# 4g.net
KiCad netlist of a schematic drawn in Altium Designer
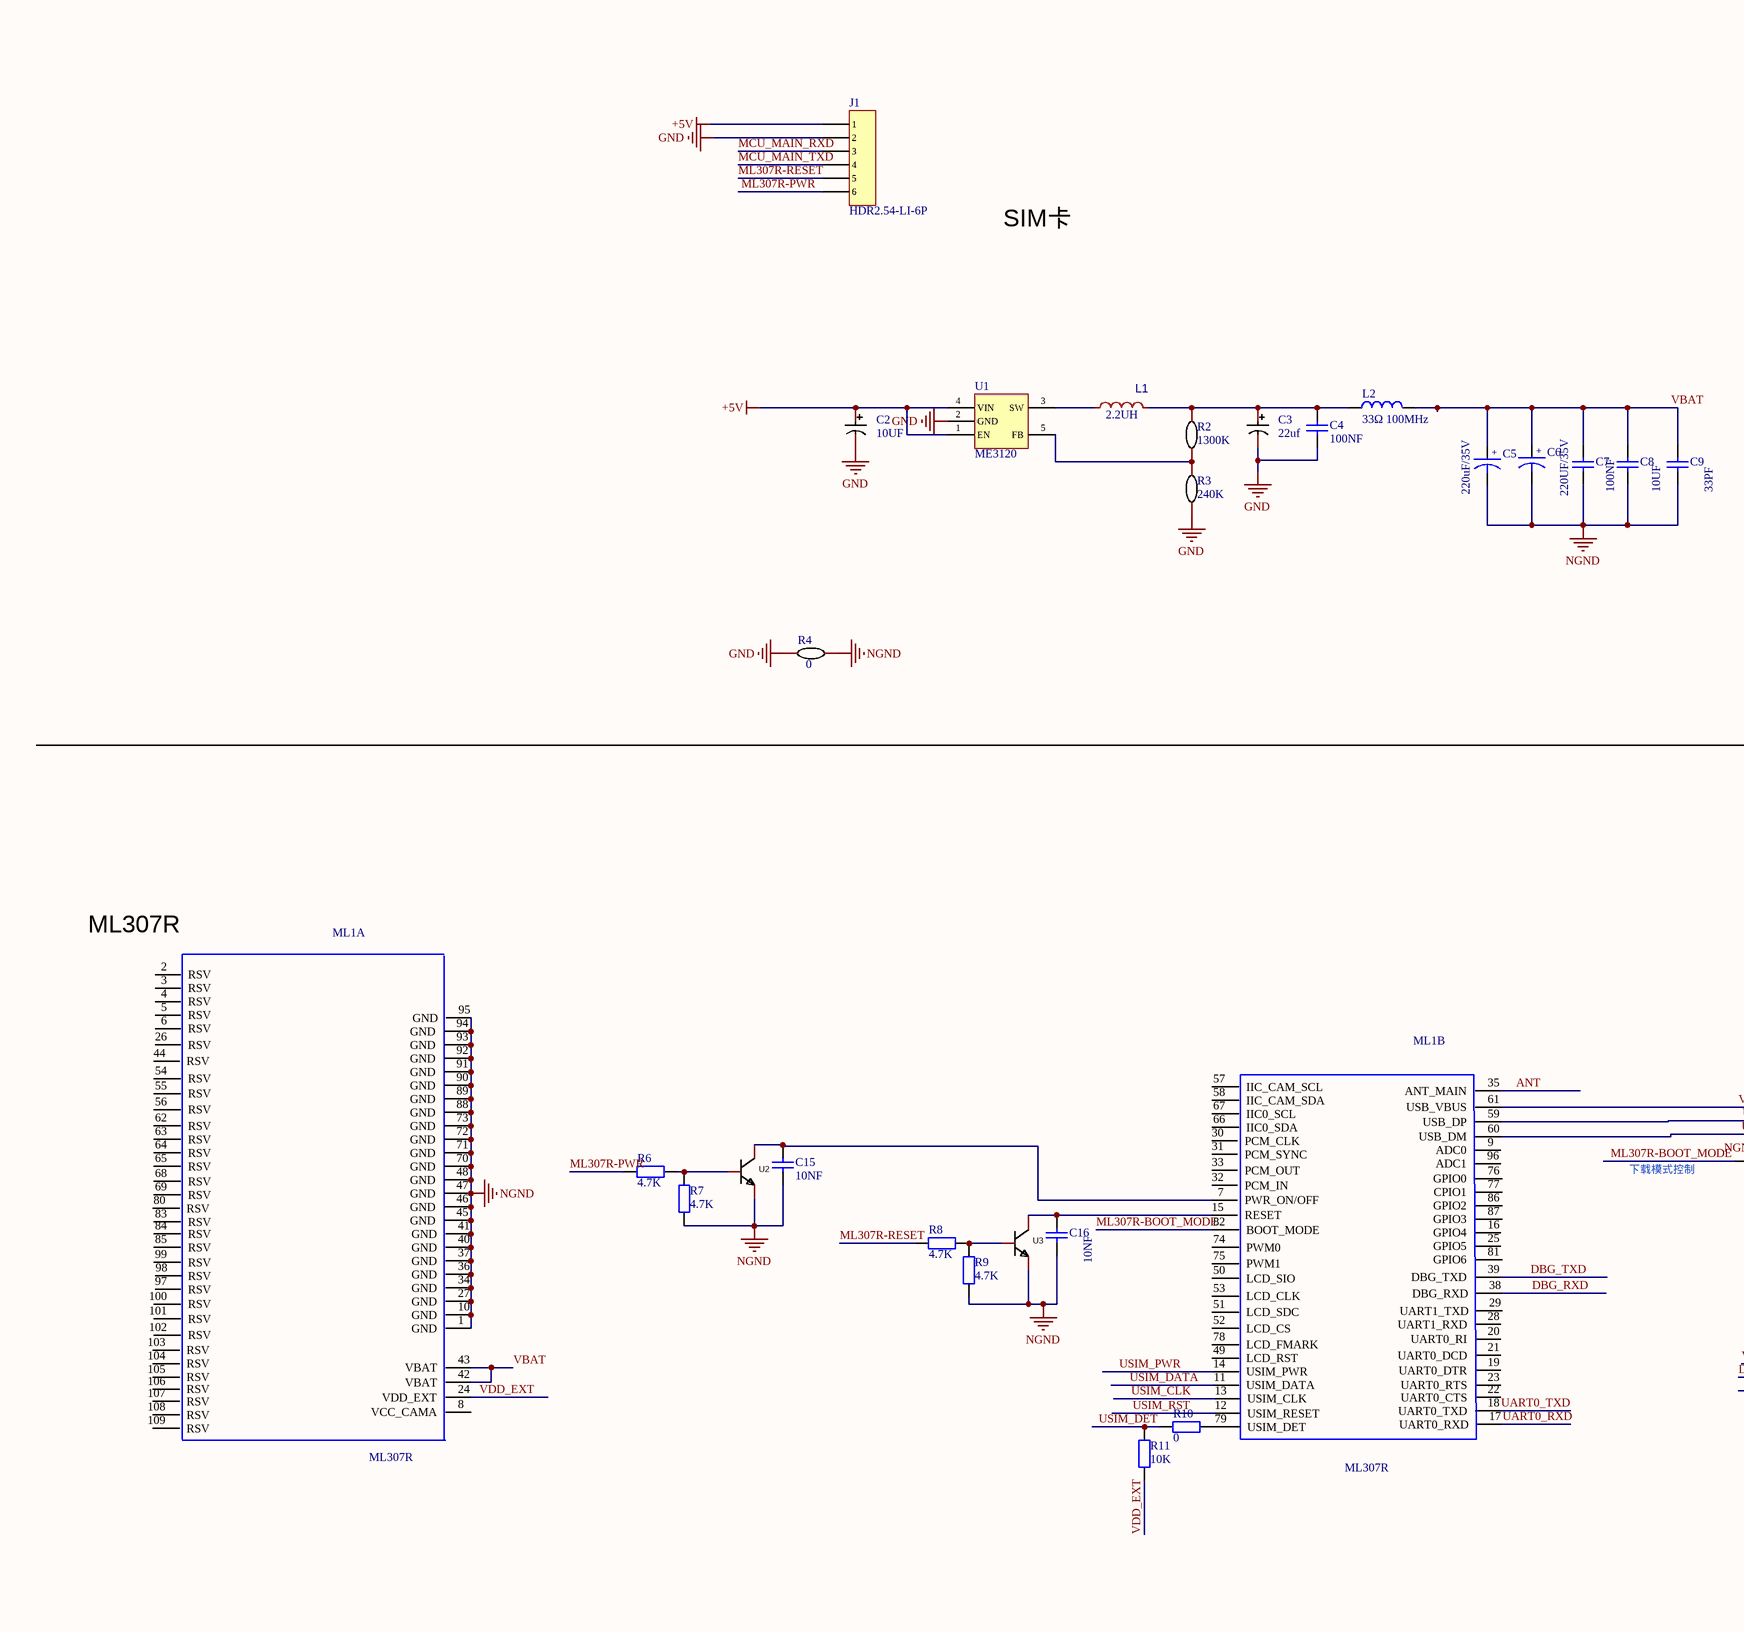
[diagram p0: 4g.SchDoc, left]
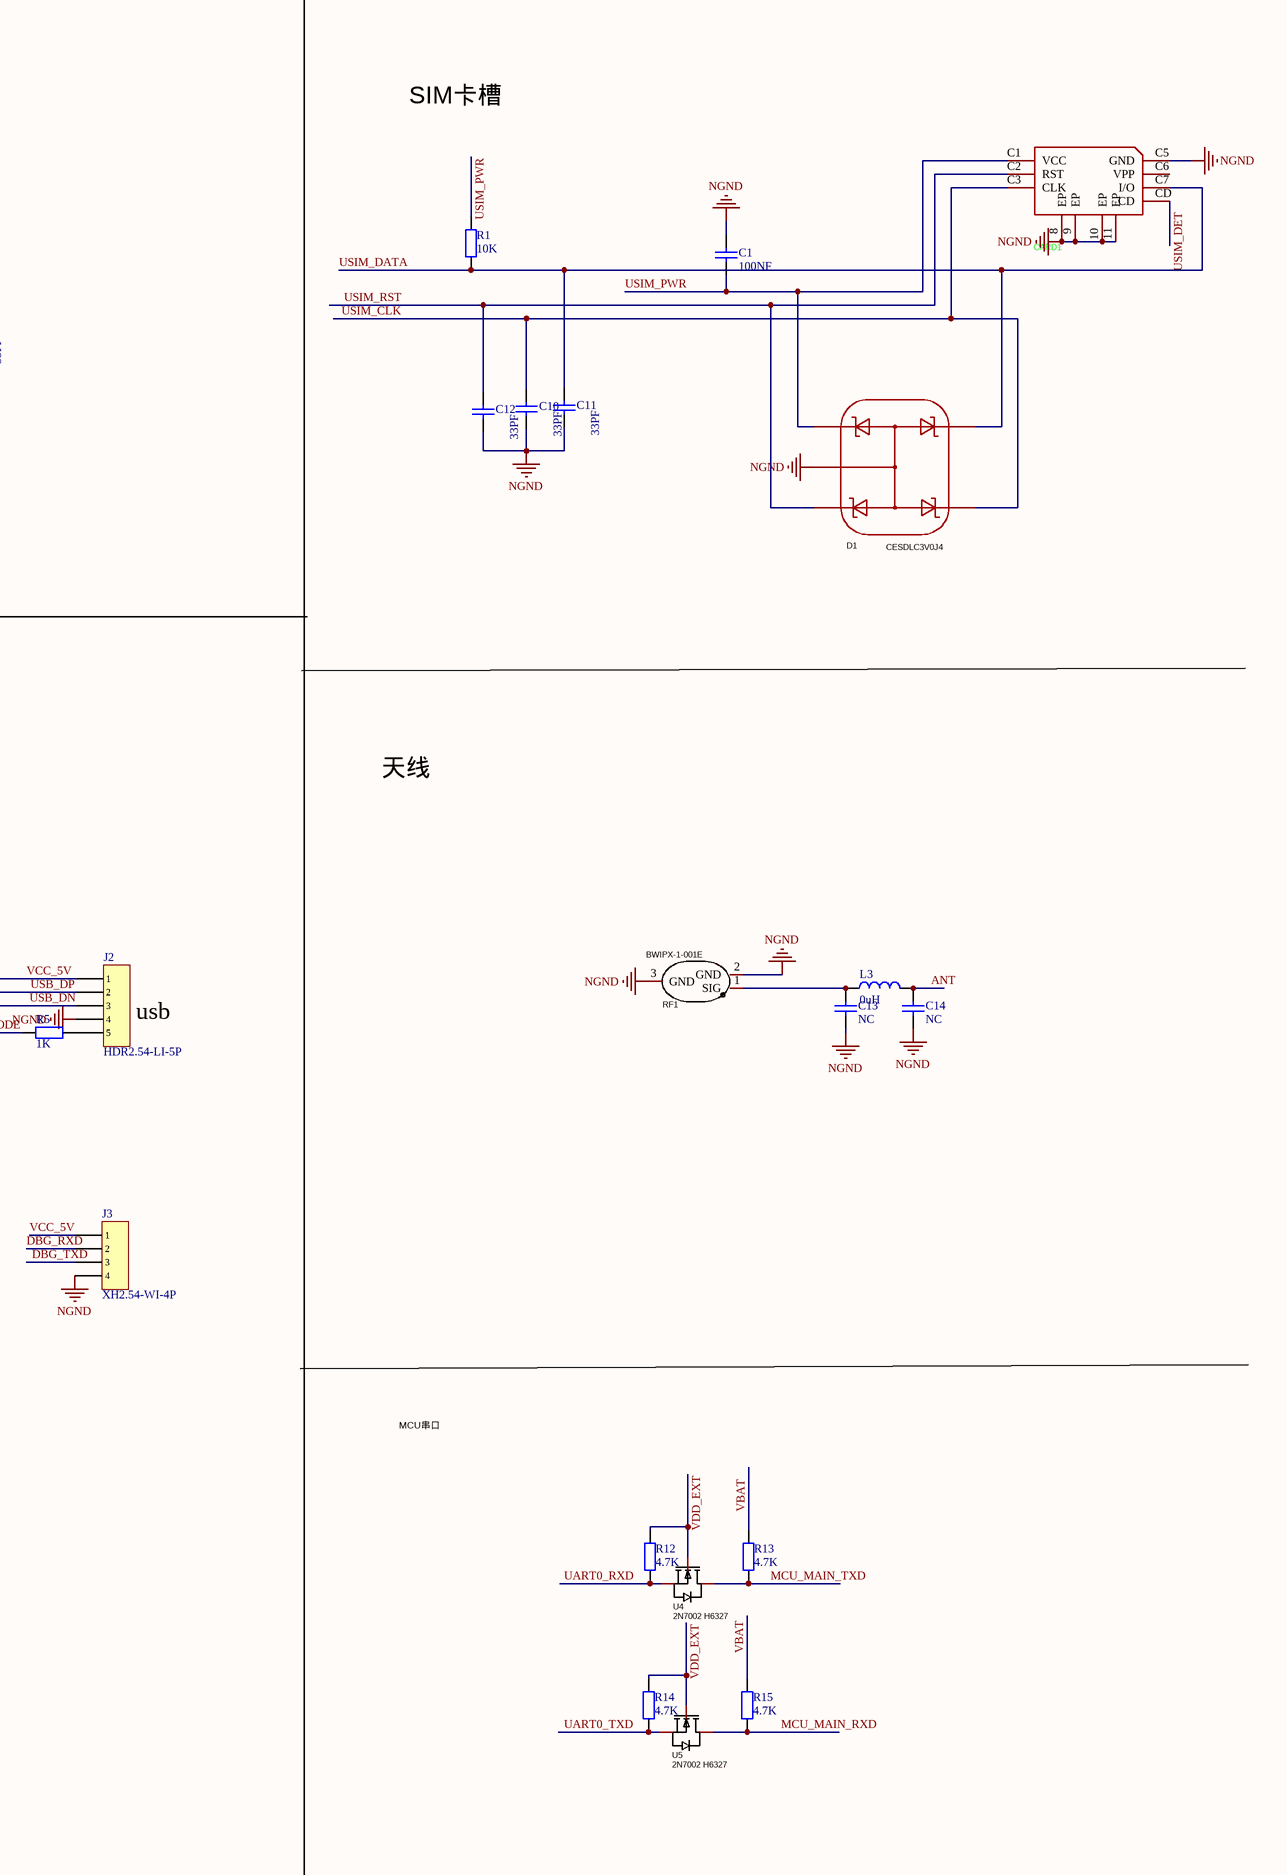
[diagram p1: 4g.SchDoc, right]

(export (version "E")
  (design (tool "Eeschema 10.0.6"))
  (components
    (comp (ref "C1")
      (value "100NF")
      (footprint "C-0603")
      (description "贴片电容")
      (libsource (lib "电容") (part "0603' 100pF 5% 50V NP0 车规"))
    )
    (comp (ref "C2")
      (value "10UF")
      (footprint "CA-3216")
      (fields
        (field (name "MANUFACTURER") "CapXon(丰宾)")
        (field (name "MANUFACTURER PART") "KF470M050E110A")
        (field (name "TOLERANCE") "±20%")
      )
      (libsource (lib "altium-import") (part "root_3_KF470M050E110A_"))
    )
    (comp (ref "C3")
      (value "22uf")
      (footprint "CA-3528")
      (fields
        (field (name "MANUFACTURER") "CapXon(丰宾)")
        (field (name "MANUFACTURER PART") "KF470M050E110A")
        (field (name "TOLERANCE") "±20%")
      )
      (libsource (lib "altium-import") (part "root_3_KF470M050E110A_"))
    )
    (comp (ref "C4")
      (value "100NF")
      (footprint "R-0603")
      (description "贴片电容")
      (libsource (lib "电容") (part "0603' 100pF 5% 50V NP0 车规"))
    )
    (comp (ref "C5")
      (value "220uF/35V")
      (footprint "CASE-B_3528")
      (description "电容")
      (libsource (lib "YLKG-51V1.0") (part "C电解电容_1"))
    )
    (comp (ref "C6")
      (value "220UF/35V")
      (footprint "CASE-B_3528")
      (description "电容")
      (libsource (lib "YLKG-51V1.0") (part "C电解电容_1"))
    )
    (comp (ref "C7")
      (value "100NF")
      (footprint "C-0603")
      (description "贴片电容")
      (libsource (lib "电容") (part "0603' 100pF 5% 50V NP0 车规"))
    )
    (comp (ref "C8")
      (value "10UF")
      (footprint "C-0603")
      (description "贴片电容")
      (libsource (lib "电容") (part "0603' 100pF 5% 50V NP0 车规"))
    )
    (comp (ref "C9")
      (value "33PF")
      (footprint "C-0603")
      (description "贴片电容")
      (libsource (lib "电容") (part "0603' 100pF 5% 50V NP0 车规"))
    )
    (comp (ref "C10")
      (value "33PF")
      (footprint "C-0603")
      (description "贴片电容")
      (libsource (lib "电容") (part "0603' 100pF 5% 50V NP0 车规"))
    )
    (comp (ref "C11")
      (value "33PF")
      (footprint "C-0603")
      (description "贴片电容")
      (libsource (lib "电容") (part "0603' 100pF 5% 50V NP0 车规"))
    )
    (comp (ref "C12")
      (value "33PF")
      (footprint "C-0603")
      (description "贴片电容")
      (libsource (lib "电容") (part "0603' 100pF 5% 50V NP0 车规"))
    )
    (comp (ref "C13")
      (value "NC")
      (footprint "C-0603")
      (description "贴片电容")
      (libsource (lib "电容") (part "0603' 100pF 5% 50V NP0 车规"))
    )
    (comp (ref "C14")
      (value "NC")
      (footprint "C-0603")
      (description "贴片电容")
      (libsource (lib "电容") (part "0603' 100pF 5% 50V NP0 车规"))
    )
    (comp (ref "C15")
      (value "10NF")
      (footprint "C-0603")
      (description "贴片电容")
      (libsource (lib "电容") (part "0603' 100pF 5% 50V NP0 车规"))
    )
    (comp (ref "C16")
      (value "10NF")
      (footprint "C-0603")
      (description "贴片电容")
      (libsource (lib "电容") (part "0603' 100pF 5% 50V NP0 车规"))
    )
    (comp (ref "CARD1")
      (value "SMN-303")
      (footprint "SIM-SMD_SMN-303")
      (fields (field (name "MANUFACTURER") "XUNPU(讯普)"))
      (libsource (lib "altium-import") (part "root_0_SMN-303_"))
    )
    (comp (ref "D1")
      (value "CESDLC3V0J4")
      (footprint "SOT-353_L2.1-W1.3-P0.65-LS2.3-BR")
      (fields (field (name "MANUFACTURER") "CJ(江苏长电/长晶)"))
      (libsource (lib "altium-import") (part "root_0_CESDLC3V0J4_"))
    )
    (comp (ref "J1")
      (value "HDR2.54-LI-6P")
      (footprint "HDR2.54-LI-6P")
      (description "直插立式单排针")
      (libsource (lib "排针排母") (part "HDR2.0-LI-6P"))
    )
    (comp (ref "J2")
      (value "HDR2.54-LI-5P")
      (footprint "2.54--5P")
      (description "直插立式单排针")
      (libsource (lib "排针排母") (part "HDR2.54-LI-5P"))
    )
    (comp (ref "J3")
      (value "XH2.54-WI-4P")
      (footprint "2.54--4P")
      (description "XH卧式直插座")
      (libsource (lib "通用连接器") (part "XH2.54-WI-4P"))
    )
    (comp (ref "L1")
      (value "2.2UH")
      (footprint "IND-SMD_L2.5-W2.0_MHCHL2520")
      (libsource (lib "altium-import") (part "root_0_FTC252012S2R2MBCA_"))
    )
    (comp (ref "L2")
      (value "33Ω 100MHz")
      (footprint "R-0805")
      (description "磁珠")
      (libsource (lib "电感") (part "0603' 33Ω 100MHz 3A 车规"))
    )
    (comp (ref "L3")
      (value "0uH")
      (footprint "R-0603")
      (description "通用电感")
      (libsource (lib "电感") (part "通用电感"))
    )
    (comp (ref "ML1")
      (value "ML307R")
      (footprint "MOD_ML307X_LGA109P")
      (description "MOD_ML307R_LCC48+LGA61_17.7mm*15.8mm")
      (fields (field (name "MANUFACTURER") "ML307X"))
      (libsource (lib "模块") (part "MOD_ML307X_LGA109P"))
    )
    (comp (ref "R1") (value "10K") (footprint "R-0603") (libsource (lib "电阻") (part "通用电阻")))
    (comp (ref "R2")
      (value "1300K")
      (footprint "R-0603")
      (description "电阻类型:厚膜电阻;阻值:0")
      (fields
        (field (name "MANUFACTURER") "UNI-ROYAL(厚声)")
        (field (name "MANUFACTURER PART") "0805W8F1002T5E")
      )
      (libsource (lib "altium-import") (part "root_3_0805W8F1002T5E_C17414_"))
    )
    (comp (ref "R3")
      (value "240K")
      (footprint "R-0603")
      (description "电阻类型:厚膜电阻;阻值:0")
      (fields
        (field (name "MANUFACTURER") "UNI-ROYAL(厚声)")
        (field (name "MANUFACTURER PART") "0805W8F1002T5E")
      )
      (libsource (lib "altium-import") (part "root_3_0805W8F1002T5E_C17414_"))
    )
    (comp (ref "R4")
      (value "0")
      (footprint "R-0805")
      (description "电阻类型:厚膜电阻;阻值:0")
      (fields
        (field (name "MANUFACTURER") "UNI-ROYAL(厚声)")
        (field (name "MANUFACTURER PART") "0805W8F1002T5E")
      )
      (libsource (lib "altium-import") (part "root_2_0805W8F1002T5E_C17414_"))
    )
    (comp (ref "R5")
      (value "1K")
      (footprint "R-0603")
      (description "贴片电阻，未编号，未录入华芯元件库，临时封装，包括0201，0402，0603，0805，1206，1210，1812，2010，2512")
      (libsource (lib "") (part "通用电阻_1"))
    )
    (comp (ref "R6")
      (value "4.7K")
      (footprint "R-0603")
      (description "贴片电阻，未编号，未录入华芯元件库，临时封装，包括0201，0402，0603，0805，1206，1210，1812，2010，2512")
      (libsource (lib "") (part "通用电阻_3"))
    )
    (comp (ref "R7")
      (value "4.7K")
      (footprint "R-0603")
      (description "贴片电阻，未编号，未录入华芯元件库，临时封装，包括0201，0402，0603，0805，1206，1210，1812，2010，2512")
      (libsource (lib "电阻") (part "通用电阻"))
    )
    (comp (ref "R8")
      (value "4.7K")
      (footprint "R-0603")
      (description "贴片电阻，未编号，未录入华芯元件库，临时封装，包括0201，0402，0603，0805，1206，1210，1812，2010，2512")
      (libsource (lib "") (part "通用电阻_3"))
    )
    (comp (ref "R9")
      (value "4.7K")
      (footprint "R-0603")
      (description "贴片电阻，未编号，未录入华芯元件库，临时封装，包括0201，0402，0603，0805，1206，1210，1812，2010，2512")
      (libsource (lib "电阻") (part "通用电阻"))
    )
    (comp (ref "R10")
      (value "0")
      (footprint "R-0603")
      (description "贴片电阻，未编号，未录入华芯元件库，临时封装，包括0201，0402，0603，0805，1206，1210，1812，2010，2512")
      (libsource (lib "") (part "通用电阻_1"))
    )
    (comp (ref "R11")
      (value "10K")
      (footprint "R-0603")
      (description "贴片电阻，未编号，未录入华芯元件库，临时封装，包括0201，0402，0603，0805，1206，1210，1812，2010，2512")
      (libsource (lib "") (part "通用电阻_2"))
    )
    (comp (ref "R12")
      (value "4.7K")
      (footprint "R-0603")
      (description "贴片电阻，未编号，未录入华芯元件库，临时封装，包括0201，0402，0603，0805，1206，1210，1812，2010，2512")
      (libsource (lib "电阻") (part "通用电阻"))
    )
    (comp (ref "R13")
      (value "4.7K")
      (footprint "R-0603")
      (description "贴片电阻，未编号，未录入华芯元件库，临时封装，包括0201，0402，0603，0805，1206，1210，1812，2010，2512")
      (libsource (lib "电阻") (part "通用电阻"))
    )
    (comp (ref "R14")
      (value "4.7K")
      (footprint "R-0603")
      (description "贴片电阻，未编号，未录入华芯元件库，临时封装，包括0201，0402，0603，0805，1206，1210，1812，2010，2512")
      (libsource (lib "电阻") (part "通用电阻"))
    )
    (comp (ref "R15")
      (value "4.7K")
      (footprint "R-0603")
      (description "贴片电阻，未编号，未录入华芯元件库，临时封装，包括0201，0402，0603，0805，1206，1210，1812，2010，2512")
      (libsource (lib "电阻") (part "通用电阻"))
    )
    (comp (ref "RF1")
      (value "BWIPX-1-001E")
      (footprint "IPEX-SMD_BWIPX-1-001E")
      (fields (field (name "MANUFACTURER") "BAT WIRELESS(蝙蝠无线)"))
      (libsource (lib "altium-import") (part "root_2_BWIPX-1-001E_"))
    )
    (comp (ref "U1")
      (value "ME3120")
      (footprint "SOT-23-5")
      (description "电源芯片")
      (libsource (lib "电源芯片") (part "ME3120"))
    )
    (comp (ref "U2")
      (value "SS8050")
      (footprint "SOT-23-3_(三极管)")
      (fields (field (name "MANUFACTURER") "宏迦橙"))
      (libsource (lib "晶体管") (part "SS8050 NPN SOT-23"))
    )
    (comp (ref "U3")
      (value "SS8050")
      (footprint "SOT-23-3_(三极管)")
      (fields (field (name "MANUFACTURER") "宏迦橙"))
      (libsource (lib "晶体管") (part "SS8050 NPN SOT-23"))
    )
    (comp (ref "U4")
      (value "2N7002 H6327")
      (footprint "PG-SOT23-3_L2.9-W1.3-P1.90-LS2.4-BR")
      (fields (field (name "MANUFACTURER") "Infineon(英飞凌)"))
      (libsource (lib "altium-import") (part "root_3_2N7002 H6327_"))
    )
    (comp (ref "U5")
      (value "2N7002 H6327")
      (footprint "PG-SOT23-3_L2.9-W1.3-P1.90-LS2.4-BR")
      (fields (field (name "MANUFACTURER") "Infineon(英飞凌)"))
      (libsource (lib "altium-import") (part "root_3_2N7002 H6327_"))
    )
  )
  (nets
    (net (code "1") (name "+5V") (class "Default")
      (node (ref "C2") (pin "1") (pinfunction "1_1") (pintype "passive"))
      (node (ref "J1") (pin "1") (pinfunction "1_1") (pintype "passive"))
      (node (ref "U1") (pin "1") (pinfunction "EN_1") (pintype "passive"))
      (node (ref "U1") (pin "4") (pinfunction "VIN_4") (pintype "passive"))
    )
    (net (code "2") (name "/ANT") (class "Default")
      (node (ref "C14") (pin "1") (pinfunction "1_1") (pintype "passive"))
      (node (ref "L3") (pin "2") (pinfunction "2_2") (pintype "passive"))
      (node (ref "ML1") (pin "35") (pinfunction "ANT_MAIN_35") (pintype "passive"))
    )
    (net (code "3") (name "/DBG_RXD") (class "Default")
      (node (ref "J3") (pin "2") (pinfunction "2_2") (pintype "passive"))
      (node (ref "ML1") (pin "38") (pinfunction "DBG_RXD_38") (pintype "passive"))
    )
    (net (code "4") (name "/DBG_TXD") (class "Default")
      (node (ref "J3") (pin "3") (pinfunction "3_3") (pintype "passive"))
      (node (ref "ML1") (pin "39") (pinfunction "DBG_TXD_39") (pintype "passive"))
    )
    (net (code "5") (name "/MCU_MAIN_RXD") (class "Default")
      (node (ref "J1") (pin "3") (pinfunction "3_3") (pintype "passive"))
      (node (ref "R15") (pin "1") (pinfunction "1_1") (pintype "passive"))
      (node (ref "U5") (pin "3") (pinfunction "D_3") (pintype "passive"))
    )
    (net (code "6") (name "/MCU_MAIN_TXD") (class "Default")
      (node (ref "J1") (pin "4") (pinfunction "4_4") (pintype "passive"))
      (node (ref "R13") (pin "1") (pinfunction "1_1") (pintype "passive"))
      (node (ref "U4") (pin "3") (pinfunction "D_3") (pintype "passive"))
    )
    (net (code "7") (name "/ML307R-BOOT_MODE") (class "Default")
      (node (ref "ML1") (pin "82") (pinfunction "BOOT_MODE_82") (pintype "passive"))
      (node (ref "R5") (pin "2") (pinfunction "2_2") (pintype "passive"))
    )
    (net (code "8") (name "/ML307R-PWR") (class "Default")
      (node (ref "J1") (pin "6") (pinfunction "6_6") (pintype "passive"))
      (node (ref "R6") (pin "1") (pinfunction "1_1") (pintype "passive"))
    )
    (net (code "9") (name "/ML307R-RESET") (class "Default")
      (node (ref "J1") (pin "5") (pinfunction "5_5") (pintype "passive"))
      (node (ref "R8") (pin "1") (pinfunction "1_1") (pintype "passive"))
    )
    (net (code "10") (name "/UART0_RXD") (class "Default")
      (node (ref "ML1") (pin "17") (pinfunction "UART0_RXD_17") (pintype "passive"))
      (node (ref "R12") (pin "1") (pinfunction "1_1") (pintype "passive"))
      (node (ref "U4") (pin "2") (pinfunction "S_2") (pintype "passive"))
    )
    (net (code "11") (name "/UART0_TXD") (class "Default")
      (node (ref "ML1") (pin "18") (pinfunction "UART0_TXD_18") (pintype "passive"))
      (node (ref "R14") (pin "1") (pinfunction "1_1") (pintype "passive"))
      (node (ref "U5") (pin "2") (pinfunction "S_2") (pintype "passive"))
    )
    (net (code "12") (name "/USB_DN") (class "Default")
      (node (ref "J2") (pin "3") (pinfunction "3_3") (pintype "passive"))
      (node (ref "ML1") (pin "60") (pinfunction "USB_DM_60") (pintype "passive"))
    )
    (net (code "13") (name "/USB_DP") (class "Default")
      (node (ref "J2") (pin "2") (pinfunction "2_2") (pintype "passive"))
      (node (ref "ML1") (pin "59") (pinfunction "USB_DP_59") (pintype "passive"))
    )
    (net (code "14") (name "/USIM_CLK") (class "Default")
      (node (ref "C10") (pin "2") (pinfunction "2_2") (pintype "passive"))
      (node (ref "CARD1") (pin "C3") (pinfunction "CLK_C3") (pintype "passive"))
      (node (ref "D1") (pin "4") (pinfunction "4_4") (pintype "passive"))
      (node (ref "ML1") (pin "13") (pinfunction "USIM_CLK_13") (pintype "passive"))
    )
    (net (code "15") (name "/USIM_DATA") (class "Default")
      (node (ref "C11") (pin "2") (pinfunction "2_2") (pintype "passive"))
      (node (ref "CARD1") (pin "C7") (pinfunction "I/O_C7") (pintype "passive"))
      (node (ref "D1") (pin "5") (pinfunction "5_5") (pintype "passive"))
      (node (ref "ML1") (pin "11") (pinfunction "USIM_DATA_11") (pintype "passive"))
      (node (ref "R1") (pin "1") (pinfunction "1_1") (pintype "passive"))
    )
    (net (code "16") (name "/USIM_DET") (class "Default")
      (node (ref "CARD1") (pin "CD") (pinfunction "CD_CD") (pintype "passive"))
      (node (ref "R10") (pin "2") (pinfunction "2_2") (pintype "passive"))
      (node (ref "R11") (pin "1") (pinfunction "1_1") (pintype "passive"))
    )
    (net (code "17") (name "/USIM_PWR") (class "Default")
      (node (ref "C1") (pin "1") (pinfunction "1_1") (pintype "passive"))
      (node (ref "CARD1") (pin "C1") (pinfunction "VCC_C1") (pintype "passive"))
      (node (ref "D1") (pin "1") (pinfunction "1_1") (pintype "passive"))
      (node (ref "ML1") (pin "14") (pinfunction "USIM_PWR_14") (pintype "passive"))
      (node (ref "R1") (pin "2") (pinfunction "2_2") (pintype "passive"))
    )
    (net (code "18") (name "/USIM_RST") (class "Default")
      (node (ref "C12") (pin "2") (pinfunction "2_2") (pintype "passive"))
      (node (ref "CARD1") (pin "C2") (pinfunction "RST_C2") (pintype "passive"))
      (node (ref "D1") (pin "3") (pinfunction "3_3") (pintype "passive"))
      (node (ref "ML1") (pin "12") (pinfunction "USIM_DET_12") (pintype "passive"))
    )
    (net (code "19") (name "/VBAT") (class "Default")
      (node (ref "C5") (pin "1") (pinfunction "1_1") (pintype "passive"))
      (node (ref "C6") (pin "1") (pinfunction "1_1") (pintype "passive"))
      (node (ref "C7") (pin "2") (pinfunction "2_2") (pintype "passive"))
      (node (ref "C8") (pin "2") (pinfunction "2_2") (pintype "passive"))
      (node (ref "C9") (pin "2") (pinfunction "2_2") (pintype "passive"))
      (node (ref "L2") (pin "2") (pinfunction "2_2") (pintype "passive"))
      (node (ref "ML1") (pin "42") (pinfunction "VBAT_42") (pintype "passive"))
      (node (ref "ML1") (pin "43") (pinfunction "VBAT_43") (pintype "passive"))
      (node (ref "R13") (pin "2") (pinfunction "2_2") (pintype "passive"))
      (node (ref "R15") (pin "2") (pinfunction "2_2") (pintype "passive"))
    )
    (net (code "20") (name "/VCC_5V") (class "Default")
      (node (ref "J2") (pin "1") (pinfunction "1_1") (pintype "passive"))
      (node (ref "J3") (pin "1") (pinfunction "1_1") (pintype "passive"))
      (node (ref "ML1") (pin "61") (pinfunction "USB_VBUS_61") (pintype "passive"))
    )
    (net (code "21") (name "/VDD_EXT") (class "Default")
      (node (ref "ML1") (pin "24") (pinfunction "VDD_EXT_24") (pintype "passive"))
      (node (ref "R11") (pin "2") (pinfunction "2_2") (pintype "passive"))
      (node (ref "R12") (pin "2") (pinfunction "2_2") (pintype "passive"))
      (node (ref "R14") (pin "2") (pinfunction "2_2") (pintype "passive"))
      (node (ref "U4") (pin "1") (pinfunction "G_1") (pintype "passive"))
      (node (ref "U5") (pin "1") (pinfunction "G_1") (pintype "passive"))
    )
    (net (code "22") (name "GND") (class "Default")
      (node (ref "C2") (pin "2") (pinfunction "2_2") (pintype "passive"))
      (node (ref "C3") (pin "2") (pinfunction "2_2") (pintype "passive"))
      (node (ref "C4") (pin "1") (pinfunction "1_1") (pintype "passive"))
      (node (ref "J1") (pin "2") (pinfunction "2_2") (pintype "passive"))
      (node (ref "R3") (pin "2") (pinfunction "2_2") (pintype "passive"))
      (node (ref "R4") (pin "2") (pinfunction "2_2") (pintype "passive"))
      (node (ref "U1") (pin "2") (pinfunction "GND_2") (pintype "passive"))
    )
    (net (code "23") (name "NGND") (class "Default")
      (node (ref "C1") (pin "2") (pinfunction "2_2") (pintype "passive"))
      (node (ref "C10") (pin "1") (pinfunction "1_1") (pintype "passive"))
      (node (ref "C11") (pin "1") (pinfunction "1_1") (pintype "passive"))
      (node (ref "C12") (pin "1") (pinfunction "1_1") (pintype "passive"))
      (node (ref "C13") (pin "2") (pinfunction "2_2") (pintype "passive"))
      (node (ref "C14") (pin "2") (pinfunction "2_2") (pintype "passive"))
      (node (ref "C15") (pin "1") (pinfunction "1_1") (pintype "passive"))
      (node (ref "C16") (pin "1") (pinfunction "1_1") (pintype "passive"))
      (node (ref "C5") (pin "2") (pinfunction "2_2") (pintype "passive"))
      (node (ref "C6") (pin "2") (pinfunction "2_2") (pintype "passive"))
      (node (ref "C7") (pin "1") (pinfunction "1_1") (pintype "passive"))
      (node (ref "C8") (pin "1") (pinfunction "1_1") (pintype "passive"))
      (node (ref "C9") (pin "1") (pinfunction "1_1") (pintype "passive"))
      (node (ref "CARD1") (pin "10") (pinfunction "EP_10") (pintype "passive"))
      (node (ref "CARD1") (pin "11") (pinfunction "EP_11") (pintype "passive"))
      (node (ref "CARD1") (pin "8") (pinfunction "EP_8") (pintype "passive"))
      (node (ref "CARD1") (pin "9") (pinfunction "EP_9") (pintype "passive"))
      (node (ref "CARD1") (pin "C5") (pinfunction "GND_C5") (pintype "passive"))
      (node (ref "D1") (pin "2") (pinfunction "2_2") (pintype "passive"))
      (node (ref "J2") (pin "4") (pinfunction "4_4") (pintype "passive"))
      (node (ref "J3") (pin "4") (pinfunction "4_4") (pintype "passive"))
      (node (ref "ML1") (pin "1") (pinfunction "GND_1") (pintype "passive"))
      (node (ref "ML1") (pin "10") (pinfunction "GND_10") (pintype "passive"))
      (node (ref "ML1") (pin "27") (pinfunction "GND_27") (pintype "passive"))
      (node (ref "ML1") (pin "34") (pinfunction "GND_34") (pintype "passive"))
      (node (ref "ML1") (pin "36") (pinfunction "GND_36") (pintype "passive"))
      (node (ref "ML1") (pin "37") (pinfunction "GND_37") (pintype "passive"))
      (node (ref "ML1") (pin "40") (pinfunction "GND_40") (pintype "passive"))
      (node (ref "ML1") (pin "41") (pinfunction "GND_41") (pintype "passive"))
      (node (ref "ML1") (pin "45") (pinfunction "GND_45") (pintype "passive"))
      (node (ref "ML1") (pin "46") (pinfunction "GND_46") (pintype "passive"))
      (node (ref "ML1") (pin "47") (pinfunction "GND_47") (pintype "passive"))
      (node (ref "ML1") (pin "48") (pinfunction "GND_48") (pintype "passive"))
      (node (ref "ML1") (pin "70") (pinfunction "GND_70") (pintype "passive"))
      (node (ref "ML1") (pin "71") (pinfunction "GND_71") (pintype "passive"))
      (node (ref "ML1") (pin "72") (pinfunction "GND_72") (pintype "passive"))
      (node (ref "ML1") (pin "73") (pinfunction "GND_73") (pintype "passive"))
      (node (ref "ML1") (pin "88") (pinfunction "GND_88") (pintype "passive"))
      (node (ref "ML1") (pin "89") (pinfunction "GND_89") (pintype "passive"))
      (node (ref "ML1") (pin "90") (pinfunction "GND_90") (pintype "passive"))
      (node (ref "ML1") (pin "91") (pinfunction "GND_91") (pintype "passive"))
      (node (ref "ML1") (pin "92") (pinfunction "GND_92") (pintype "passive"))
      (node (ref "ML1") (pin "93") (pinfunction "GND_93") (pintype "passive"))
      (node (ref "ML1") (pin "94") (pinfunction "GND_94") (pintype "passive"))
      (node (ref "ML1") (pin "95") (pinfunction "GND_95") (pintype "passive"))
      (node (ref "R4") (pin "1") (pinfunction "1_1") (pintype "passive"))
      (node (ref "R7") (pin "1") (pinfunction "1_1") (pintype "passive"))
      (node (ref "R9") (pin "1") (pinfunction "1_1") (pintype "passive"))
      (node (ref "RF1") (pin "2") (pinfunction "GND_2") (pintype "passive"))
      (node (ref "RF1") (pin "3") (pinfunction "GND_3") (pintype "passive"))
      (node (ref "U2") (pin "2") (pinfunction "E_2") (pintype "passive"))
      (node (ref "U3") (pin "2") (pinfunction "E_2") (pintype "passive"))
    )
    (net (code "24") (name "Net-(C3-Pad1)") (class "Default")
      (node (ref "C3") (pin "1") (pinfunction "1_1") (pintype "passive"))
      (node (ref "C4") (pin "2") (pinfunction "2_2") (pintype "passive"))
      (node (ref "L1") (pin "2") (pinfunction "2_2") (pintype "passive"))
      (node (ref "L2") (pin "1") (pinfunction "1_1") (pintype "passive"))
      (node (ref "R2") (pin "1") (pinfunction "1_1") (pintype "passive"))
    )
    (net (code "25") (name "Net-(J2-Pad5)") (class "Default")
      (node (ref "J2") (pin "5") (pinfunction "5_5") (pintype "passive"))
      (node (ref "R5") (pin "1") (pinfunction "1_1") (pintype "passive"))
    )
    (net (code "26") (name "Net-(ML1B-PWR_ON{slash}OFF)") (class "Default")
      (node (ref "C15") (pin "2") (pinfunction "2_2") (pintype "passive"))
      (node (ref "ML1") (pin "7") (pinfunction "PWR_ON/OFF_7") (pintype "passive"))
      (node (ref "U2") (pin "3") (pinfunction "C_3") (pintype "passive"))
    )
    (net (code "27") (name "Net-(ML1B-RESET)") (class "Default")
      (node (ref "C16") (pin "2") (pinfunction "2_2") (pintype "passive"))
      (node (ref "ML1") (pin "15") (pinfunction "RESET_15") (pintype "passive"))
      (node (ref "U3") (pin "3") (pinfunction "C_3") (pintype "passive"))
    )
    (net (code "28") (name "Net-(ML1B-USIM_DET-Pad79)") (class "Default")
      (node (ref "ML1") (pin "79") (pinfunction "USIM_DET_79") (pintype "passive"))
      (node (ref "R10") (pin "1") (pinfunction "1_1") (pintype "passive"))
    )
    (net (code "29") (name "Net-(RF1-SIG)") (class "Default")
      (node (ref "C13") (pin "1") (pinfunction "1_1") (pintype "passive"))
      (node (ref "L3") (pin "1") (pinfunction "1_1") (pintype "passive"))
      (node (ref "RF1") (pin "1") (pinfunction "SIG_1") (pintype "passive"))
    )
    (net (code "30") (name "Net-(U1-FB)") (class "Default")
      (node (ref "R2") (pin "2") (pinfunction "2_2") (pintype "passive"))
      (node (ref "R3") (pin "1") (pinfunction "1_1") (pintype "passive"))
      (node (ref "U1") (pin "5") (pinfunction "FB_5") (pintype "passive"))
    )
    (net (code "31") (name "Net-(U1-SW)") (class "Default")
      (node (ref "L1") (pin "1") (pinfunction "1_1") (pintype "passive"))
      (node (ref "U1") (pin "3") (pinfunction "SW_3") (pintype "passive"))
    )
    (net (code "32") (name "Net-(U2-B)") (class "Default")
      (node (ref "R6") (pin "2") (pinfunction "2_2") (pintype "passive"))
      (node (ref "R7") (pin "2") (pinfunction "2_2") (pintype "passive"))
      (node (ref "U2") (pin "1") (pinfunction "B_1") (pintype "passive"))
    )
    (net (code "33") (name "Net-(U3-B)") (class "Default")
      (node (ref "R8") (pin "2") (pinfunction "2_2") (pintype "passive"))
      (node (ref "R9") (pin "2") (pinfunction "2_2") (pintype "passive"))
      (node (ref "U3") (pin "1") (pinfunction "B_1") (pintype "passive"))
    )
    (net (code "34") (name "unconnected-(CARD1-VPP-PadC6)") (class "Default")
      (node (ref "CARD1") (pin "C6") (pinfunction "VPP_C6") (pintype "passive"))
    )
    (net (code "35") (name "unconnected-(ML1A-RSV-Pad2)") (class "Default")
      (node (ref "ML1") (pin "2") (pinfunction "RSV_2") (pintype "passive"))
    )
    (net (code "36") (name "unconnected-(ML1A-RSV-Pad3)") (class "Default")
      (node (ref "ML1") (pin "3") (pinfunction "RSV_3") (pintype "passive"))
    )
    (net (code "37") (name "unconnected-(ML1A-RSV-Pad4)") (class "Default")
      (node (ref "ML1") (pin "4") (pinfunction "RSV_4") (pintype "passive"))
    )
    (net (code "38") (name "unconnected-(ML1A-RSV-Pad5)") (class "Default")
      (node (ref "ML1") (pin "5") (pinfunction "RSV_5") (pintype "passive"))
    )
    (net (code "39") (name "unconnected-(ML1A-RSV-Pad6)") (class "Default")
      (node (ref "ML1") (pin "6") (pinfunction "RSV_6") (pintype "passive"))
    )
    (net (code "40") (name "unconnected-(ML1A-RSV-Pad26)") (class "Default")
      (node (ref "ML1") (pin "26") (pinfunction "RSV_26") (pintype "passive"))
    )
    (net (code "41") (name "unconnected-(ML1A-RSV-Pad44)") (class "Default")
      (node (ref "ML1") (pin "44") (pinfunction "RSV_44") (pintype "passive"))
    )
    (net (code "42") (name "unconnected-(ML1A-RSV-Pad54)") (class "Default")
      (node (ref "ML1") (pin "54") (pinfunction "RSV_54") (pintype "passive"))
    )
    (net (code "43") (name "unconnected-(ML1A-RSV-Pad55)") (class "Default")
      (node (ref "ML1") (pin "55") (pinfunction "RSV_55") (pintype "passive"))
    )
    (net (code "44") (name "unconnected-(ML1A-RSV-Pad56)") (class "Default")
      (node (ref "ML1") (pin "56") (pinfunction "RSV_56") (pintype "passive"))
    )
    (net (code "45") (name "unconnected-(ML1A-RSV-Pad62)") (class "Default")
      (node (ref "ML1") (pin "62") (pinfunction "RSV_62") (pintype "passive"))
    )
    (net (code "46") (name "unconnected-(ML1A-RSV-Pad63)") (class "Default")
      (node (ref "ML1") (pin "63") (pinfunction "RSV_63") (pintype "passive"))
    )
    (net (code "47") (name "unconnected-(ML1A-RSV-Pad64)") (class "Default")
      (node (ref "ML1") (pin "64") (pinfunction "RSV_64") (pintype "passive"))
    )
    (net (code "48") (name "unconnected-(ML1A-RSV-Pad65)") (class "Default")
      (node (ref "ML1") (pin "65") (pinfunction "RSV_65") (pintype "passive"))
    )
    (net (code "49") (name "unconnected-(ML1A-RSV-Pad68)") (class "Default")
      (node (ref "ML1") (pin "68") (pinfunction "RSV_68") (pintype "passive"))
    )
    (net (code "50") (name "unconnected-(ML1A-RSV-Pad69)") (class "Default")
      (node (ref "ML1") (pin "69") (pinfunction "RSV_69") (pintype "passive"))
    )
    (net (code "51") (name "unconnected-(ML1A-RSV-Pad80)") (class "Default")
      (node (ref "ML1") (pin "80") (pinfunction "RSV_80") (pintype "passive"))
    )
    (net (code "52") (name "unconnected-(ML1A-RSV-Pad83)") (class "Default")
      (node (ref "ML1") (pin "83") (pinfunction "RSV_83") (pintype "passive"))
    )
    (net (code "53") (name "unconnected-(ML1A-RSV-Pad84)") (class "Default")
      (node (ref "ML1") (pin "84") (pinfunction "RSV_84") (pintype "passive"))
    )
    (net (code "54") (name "unconnected-(ML1A-RSV-Pad85)") (class "Default")
      (node (ref "ML1") (pin "85") (pinfunction "RSV_85") (pintype "passive"))
    )
    (net (code "55") (name "unconnected-(ML1A-RSV-Pad97)") (class "Default")
      (node (ref "ML1") (pin "97") (pinfunction "RSV_97") (pintype "passive"))
    )
    (net (code "56") (name "unconnected-(ML1A-RSV-Pad98)") (class "Default")
      (node (ref "ML1") (pin "98") (pinfunction "RSV_98") (pintype "passive"))
    )
    (net (code "57") (name "unconnected-(ML1A-RSV-Pad99)") (class "Default")
      (node (ref "ML1") (pin "99") (pinfunction "RSV_99") (pintype "passive"))
    )
    (net (code "58") (name "unconnected-(ML1A-RSV-Pad100)") (class "Default")
      (node (ref "ML1") (pin "100") (pinfunction "RSV_100") (pintype "passive"))
    )
    (net (code "59") (name "unconnected-(ML1A-RSV-Pad101)") (class "Default")
      (node (ref "ML1") (pin "101") (pinfunction "RSV_101") (pintype "passive"))
    )
    (net (code "60") (name "unconnected-(ML1A-RSV-Pad102)") (class "Default")
      (node (ref "ML1") (pin "102") (pinfunction "RSV_102") (pintype "passive"))
    )
    (net (code "61") (name "unconnected-(ML1A-RSV-Pad103)") (class "Default")
      (node (ref "ML1") (pin "103") (pinfunction "RSV_103") (pintype "passive"))
    )
    (net (code "62") (name "unconnected-(ML1A-RSV-Pad104)") (class "Default")
      (node (ref "ML1") (pin "104") (pinfunction "RSV_104") (pintype "passive"))
    )
    (net (code "63") (name "unconnected-(ML1A-RSV-Pad105)") (class "Default")
      (node (ref "ML1") (pin "105") (pinfunction "RSV_105") (pintype "passive"))
    )
    (net (code "64") (name "unconnected-(ML1A-RSV-Pad106)") (class "Default")
      (node (ref "ML1") (pin "106") (pinfunction "RSV_106") (pintype "passive"))
    )
    (net (code "65") (name "unconnected-(ML1A-RSV-Pad107)") (class "Default")
      (node (ref "ML1") (pin "107") (pinfunction "RSV_107") (pintype "passive"))
    )
    (net (code "66") (name "unconnected-(ML1A-RSV-Pad108)") (class "Default")
      (node (ref "ML1") (pin "108") (pinfunction "RSV_108") (pintype "passive"))
    )
    (net (code "67") (name "unconnected-(ML1A-RSV-Pad109)") (class "Default")
      (node (ref "ML1") (pin "109") (pinfunction "RSV_109") (pintype "passive"))
    )
    (net (code "68") (name "unconnected-(ML1A-VCC_CAMA-Pad8)") (class "Default")
      (node (ref "ML1") (pin "8") (pinfunction "VCC_CAMA_8") (pintype "passive"))
    )
    (net (code "69") (name "unconnected-(ML1B-ADC0-Pad9)") (class "Default")
      (node (ref "ML1") (pin "9") (pinfunction "ADC0_9") (pintype "passive"))
    )
    (net (code "70") (name "unconnected-(ML1B-ADC1-Pad96)") (class "Default")
      (node (ref "ML1") (pin "96") (pinfunction "ADC1_96") (pintype "passive"))
    )
    (net (code "71") (name "unconnected-(ML1B-CPIO1-Pad77)") (class "Default")
      (node (ref "ML1") (pin "77") (pinfunction "CPIO1_77") (pintype "passive"))
    )
    (net (code "72") (name "unconnected-(ML1B-GPIO0-Pad76)") (class "Default")
      (node (ref "ML1") (pin "76") (pinfunction "GPIO0_76") (pintype "passive"))
    )
    (net (code "73") (name "unconnected-(ML1B-GPIO2-Pad86)") (class "Default")
      (node (ref "ML1") (pin "86") (pinfunction "GPIO2_86") (pintype "passive"))
    )
    (net (code "74") (name "unconnected-(ML1B-GPIO3-Pad87)") (class "Default")
      (node (ref "ML1") (pin "87") (pinfunction "GPIO3_87") (pintype "passive"))
    )
    (net (code "75") (name "unconnected-(ML1B-GPIO4-Pad16)") (class "Default")
      (node (ref "ML1") (pin "16") (pinfunction "GPIO4_16") (pintype "passive"))
    )
    (net (code "76") (name "unconnected-(ML1B-GPIO5-Pad25)") (class "Default")
      (node (ref "ML1") (pin "25") (pinfunction "GPIO5_25") (pintype "passive"))
    )
    (net (code "77") (name "unconnected-(ML1B-GPIO6-Pad81)") (class "Default")
      (node (ref "ML1") (pin "81") (pinfunction "GPIO6_81") (pintype "passive"))
    )
    (net (code "78") (name "unconnected-(ML1B-IIC0_SCL-Pad67)") (class "Default")
      (node (ref "ML1") (pin "67") (pinfunction "IIC0_SCL_67") (pintype "passive"))
    )
    (net (code "79") (name "unconnected-(ML1B-IIC0_SDA-Pad66)") (class "Default")
      (node (ref "ML1") (pin "66") (pinfunction "IIC0_SDA_66") (pintype "passive"))
    )
    (net (code "80") (name "unconnected-(ML1B-IIC_CAM_SCL-Pad57)") (class "Default")
      (node (ref "ML1") (pin "57") (pinfunction "IIC_CAM_SCL_57") (pintype "passive"))
    )
    (net (code "81") (name "unconnected-(ML1B-IIC_CAM_SDA-Pad58)") (class "Default")
      (node (ref "ML1") (pin "58") (pinfunction "IIC_CAM_SDA_58") (pintype "passive"))
    )
    (net (code "82") (name "unconnected-(ML1B-LCD_CLK-Pad53)") (class "Default")
      (node (ref "ML1") (pin "53") (pinfunction "LCD_CLK_53") (pintype "passive"))
    )
    (net (code "83") (name "unconnected-(ML1B-LCD_CS-Pad52)") (class "Default")
      (node (ref "ML1") (pin "52") (pinfunction "LCD_CS_52") (pintype "passive"))
    )
    (net (code "84") (name "unconnected-(ML1B-LCD_FMARK-Pad78)") (class "Default")
      (node (ref "ML1") (pin "78") (pinfunction "LCD_FMARK_78") (pintype "passive"))
    )
    (net (code "85") (name "unconnected-(ML1B-LCD_RST-Pad49)") (class "Default")
      (node (ref "ML1") (pin "49") (pinfunction "LCD_RST_49") (pintype "passive"))
    )
    (net (code "86") (name "unconnected-(ML1B-LCD_SDC-Pad51)") (class "Default")
      (node (ref "ML1") (pin "51") (pinfunction "LCD_SDC_51") (pintype "passive"))
    )
    (net (code "87") (name "unconnected-(ML1B-LCD_SIO-Pad50)") (class "Default")
      (node (ref "ML1") (pin "50") (pinfunction "LCD_SIO_50") (pintype "passive"))
    )
    (net (code "88") (name "unconnected-(ML1B-PCM_CLK-Pad30)") (class "Default")
      (node (ref "ML1") (pin "30") (pinfunction "PCM_CLK_30") (pintype "passive"))
    )
    (net (code "89") (name "unconnected-(ML1B-PCM_IN-Pad32)") (class "Default")
      (node (ref "ML1") (pin "32") (pinfunction "PCM_IN_32") (pintype "passive"))
    )
    (net (code "90") (name "unconnected-(ML1B-PCM_OUT-Pad33)") (class "Default")
      (node (ref "ML1") (pin "33") (pinfunction "PCM_OUT_33") (pintype "passive"))
    )
    (net (code "91") (name "unconnected-(ML1B-PCM_SYNC-Pad31)") (class "Default")
      (node (ref "ML1") (pin "31") (pinfunction "PCM_SYNC_31") (pintype "passive"))
    )
    (net (code "92") (name "unconnected-(ML1B-PWM0-Pad74)") (class "Default")
      (node (ref "ML1") (pin "74") (pinfunction "PWM0_74") (pintype "passive"))
    )
    (net (code "93") (name "unconnected-(ML1B-PWM1-Pad75)") (class "Default")
      (node (ref "ML1") (pin "75") (pinfunction "PWM1_75") (pintype "passive"))
    )
    (net (code "94") (name "unconnected-(ML1B-UART0_CTS-Pad22)") (class "Default")
      (node (ref "ML1") (pin "22") (pinfunction "UART0_CTS_22") (pintype "passive"))
    )
    (net (code "95") (name "unconnected-(ML1B-UART0_DCD-Pad21)") (class "Default")
      (node (ref "ML1") (pin "21") (pinfunction "UART0_DCD_21") (pintype "passive"))
    )
    (net (code "96") (name "unconnected-(ML1B-UART0_DTR-Pad19)") (class "Default")
      (node (ref "ML1") (pin "19") (pinfunction "UART0_DTR_19") (pintype "passive"))
    )
    (net (code "97") (name "unconnected-(ML1B-UART0_RI-Pad20)") (class "Default")
      (node (ref "ML1") (pin "20") (pinfunction "UART0_RI_20") (pintype "passive"))
    )
    (net (code "98") (name "unconnected-(ML1B-UART0_RTS-Pad23)") (class "Default")
      (node (ref "ML1") (pin "23") (pinfunction "UART0_RTS_23") (pintype "passive"))
    )
    (net (code "99") (name "unconnected-(ML1B-UART1_RXD-Pad28)") (class "Default")
      (node (ref "ML1") (pin "28") (pinfunction "UART1_RXD_28") (pintype "passive"))
    )
    (net (code "100") (name "unconnected-(ML1B-UART1_TXD-Pad29)") (class "Default")
      (node (ref "ML1") (pin "29") (pinfunction "UART1_TXD_29") (pintype "passive"))
    )
  )
)
